# RVP_OVP_LC.net
KiCad netlist of a schematic drawn in Altium Designer
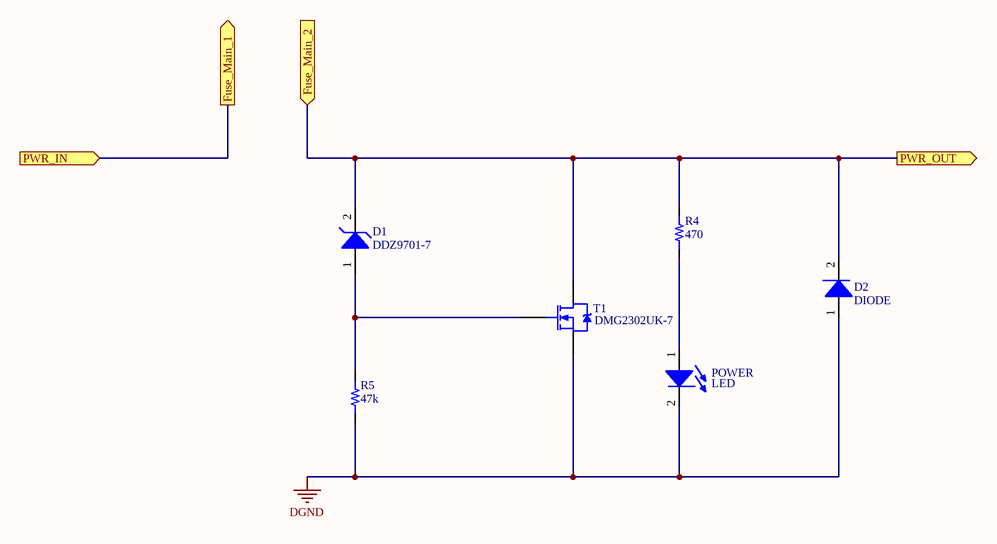
[diagram p0: RVP_OVP_LC.SchDoc]

(export (version "E")
  (design (tool "Eeschema 10.0.6"))
  (components
    (comp (ref "D1")
      (value "DDZ9701-7")
      (footprint "SOD123F")
      (description "Zener Diode 14V 500mW ±5% Surface Mount SOD-123")
      (fields (field (name "POWER") "500mW"))
      (libsource (lib "Altium-Lib") (part "Zener"))
    )
    (comp (ref "D2")
      (value "DIODE")
      (footprint "SOD-128")
      (description "DIODE SCHOTTKY 30V 5A TMINIP2")
      (fields (field (name "POWER") "30V") (field (name "MFRPARTNO") "DB2431200L"))
      (libsource (lib "Altium-Lib") (part "DIODE"))
    )
    (comp (ref "POWER") (value "LED") (footprint "0805_LED") (libsource (lib "Altium-Lib") (part "LED")))
    (comp (ref "R4")
      (value "470")
      (footprint "RES 0603/1608")
      (fields
        (field (name "TOLERANCE") "5%")
        (field (name "POWER") "1/10W")
        (field (name "Comment") "Resistor 470 0603 1/10W 5%")
        (field (name "CREATED_BY") "Nick Mah")
      )
      (libsource (lib "Altium-Lib") (part "Resistor"))
    )
    (comp (ref "R5")
      (value "47k")
      (footprint "RES 0603/1608")
      (fields
        (field (name "TOLERANCE") "5%")
        (field (name "POWER") "1/10W")
        (field (name "Comment") "Resistor 47k 0603 1/10W 5%")
        (field (name "CREATED_BY") "Nick Mah")
      )
      (libsource (lib "Altium-Lib") (part "Resistor"))
    )
    (comp (ref "T1")
      (value "DMG2302UK-7")
      (footprint "SOT23-3")
      (description "MOSFET N-CHANNEL 30V 5A SOT23")
      (fields (field (name "CREATED_BY") "Angel"))
      (libsource (lib "Altium-Lib") (part "DMG2302UK-7"))
    )
  )
  (nets
    (net (code "2") (name "/Fuse_Main_2") (class "Default")
      (node (ref "D1") (pin "2") (pinfunction "K_2") (pintype "passive"))
      (node (ref "D2") (pin "2") (pinfunction "K_2") (pintype "passive"))
      (node (ref "R4") (pin "2") (pinfunction "2_2") (pintype "passive"))
      (node (ref "T1") (pin "3") (pinfunction "D_3") (pintype "passive"))
    )
    (net (code "3") (name "DGND") (class "Default")
      (node (ref "D2") (pin "1") (pinfunction "A_1") (pintype "passive"))
      (node (ref "POWER") (pin "2") (pinfunction "K_2") (pintype "passive"))
      (node (ref "R5") (pin "1") (pinfunction "1_1") (pintype "passive"))
      (node (ref "T1") (pin "2") (pinfunction "S_2") (pintype "passive"))
    )
    (net (code "4") (name "Net-(D1-A)") (class "Default")
      (node (ref "D1") (pin "1") (pinfunction "A_1") (pintype "passive"))
      (node (ref "R5") (pin "2") (pinfunction "2_2") (pintype "passive"))
      (node (ref "T1") (pin "1") (pinfunction "G_1") (pintype "passive"))
    )
    (net (code "5") (name "Net-(POWER-A)") (class "Default")
      (node (ref "POWER") (pin "1") (pinfunction "A_1") (pintype "passive"))
      (node (ref "R4") (pin "1") (pinfunction "1_1") (pintype "passive"))
    )
  )
)
